# acs.net
KiCad netlist of a schematic drawn in EAGLE
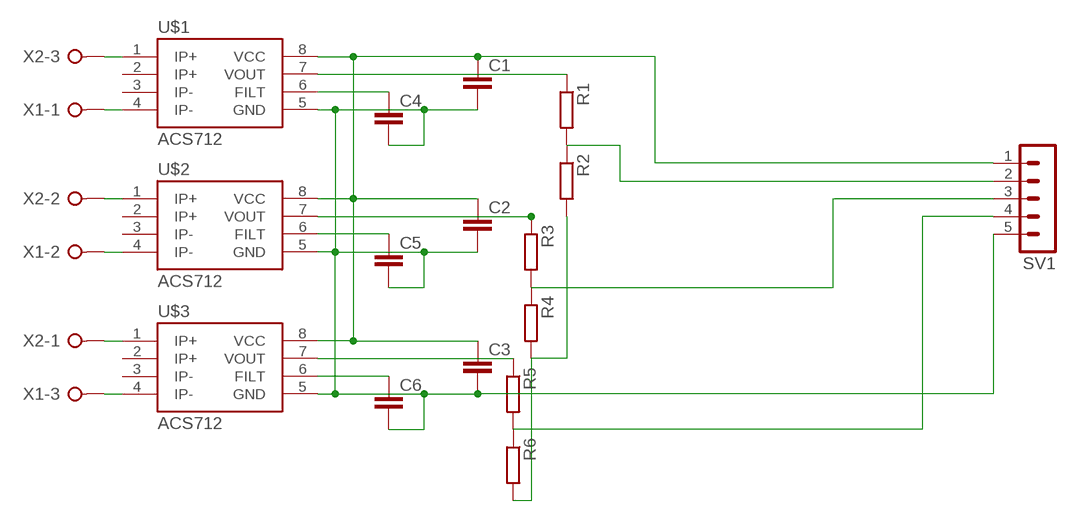
[diagram p0: schematic, sheet 1]

(export (version "E")
  (design (tool "Eeschema 10.0.6"))
  (components
    (comp (ref "C1")
      (value "C-EUC0603")
      (footprint "eagle-import:C0603")
      (libsource (lib "eagle-import") (part "C-EUC0603"))
    )
    (comp (ref "C2")
      (value "C-EUC0603")
      (footprint "eagle-import:C0603")
      (libsource (lib "eagle-import") (part "C-EUC0603"))
    )
    (comp (ref "C3")
      (value "C-EUC0603")
      (footprint "eagle-import:C0603")
      (libsource (lib "eagle-import") (part "C-EUC0603"))
    )
    (comp (ref "C4")
      (value "C-EUC0603")
      (footprint "eagle-import:C0603")
      (libsource (lib "eagle-import") (part "C-EUC0603"))
    )
    (comp (ref "C5")
      (value "C-EUC0603")
      (footprint "eagle-import:C0603")
      (libsource (lib "eagle-import") (part "C-EUC0603"))
    )
    (comp (ref "C6")
      (value "C-EUC0603")
      (footprint "eagle-import:C0603")
      (libsource (lib "eagle-import") (part "C-EUC0603"))
    )
    (comp (ref "R1")
      (value "R-EU_R0603")
      (footprint "eagle-import:R0603")
      (libsource (lib "eagle-import") (part "R-EU_R0603"))
    )
    (comp (ref "R2")
      (value "R-EU_R0603")
      (footprint "eagle-import:R0603")
      (libsource (lib "eagle-import") (part "R-EU_R0603"))
    )
    (comp (ref "R3")
      (value "R-EU_R0603")
      (footprint "eagle-import:R0603")
      (libsource (lib "eagle-import") (part "R-EU_R0603"))
    )
    (comp (ref "R4")
      (value "R-EU_R0603")
      (footprint "eagle-import:R0603")
      (libsource (lib "eagle-import") (part "R-EU_R0603"))
    )
    (comp (ref "R5")
      (value "R-EU_R0603")
      (footprint "eagle-import:R0603")
      (libsource (lib "eagle-import") (part "R-EU_R0603"))
    )
    (comp (ref "R6")
      (value "R-EU_R0603")
      (footprint "eagle-import:R0603")
      (libsource (lib "eagle-import") (part "R-EU_R0603"))
    )
    (comp (ref "SV1")
      (value "MA05-1")
      (footprint "eagle-import:MA05-1")
      (libsource (lib "eagle-import") (part "MA05-1"))
    )
    (comp (ref "U$1")
      (value "ACS712")
      (footprint "eagle-import:SO08")
      (libsource (lib "eagle-import") (part "ACS712"))
    )
    (comp (ref "U$2")
      (value "ACS712")
      (footprint "eagle-import:SO08")
      (libsource (lib "eagle-import") (part "ACS712"))
    )
    (comp (ref "U$3")
      (value "ACS712")
      (footprint "eagle-import:SO08")
      (libsource (lib "eagle-import") (part "ACS712"))
    )
    (comp (ref "X1")
      (value "W237-03P")
      (footprint "eagle-import:W237-133")
      (libsource (lib "eagle-import") (part "W237-03P"))
    )
    (comp (ref "X2")
      (value "W237-03P")
      (footprint "eagle-import:W237-133")
      (libsource (lib "eagle-import") (part "W237-03P"))
    )
  )
  (nets
    (net (code "1") (name "Net-(R1-Pad2)") (class "Default")
      (node (ref "R1") (pin "2") (pinfunction "2_2") (pintype "passive"))
      (node (ref "R2") (pin "1") (pinfunction "1_1") (pintype "passive"))
      (node (ref "SV1") (pin "2") (pinfunction "2_2") (pintype "passive"))
    )
    (net (code "2") (name "Net-(R2-Pad2)") (class "Default")
      (node (ref "R2") (pin "2") (pinfunction "2_2") (pintype "passive"))
      (node (ref "R4") (pin "2") (pinfunction "2_2") (pintype "passive"))
      (node (ref "R6") (pin "2") (pinfunction "2_2") (pintype "passive"))
    )
    (net (code "3") (name "Net-(R3-Pad2)") (class "Default")
      (node (ref "R3") (pin "2") (pinfunction "2_2") (pintype "passive"))
      (node (ref "R4") (pin "1") (pinfunction "1_1") (pintype "passive"))
      (node (ref "SV1") (pin "3") (pinfunction "3_3") (pintype "passive"))
    )
    (net (code "4") (name "Net-(R5-Pad2)") (class "Default")
      (node (ref "R5") (pin "2") (pinfunction "2_2") (pintype "passive"))
      (node (ref "R6") (pin "1") (pinfunction "1_1") (pintype "passive"))
      (node (ref "SV1") (pin "4") (pinfunction "4_4") (pintype "passive"))
    )
    (net (code "5") (name "Net-(U$1-FILT)") (class "Default")
      (node (ref "C4") (pin "1") (pinfunction "1_1") (pintype "passive"))
      (node (ref "U$1") (pin "6") (pinfunction "FILT_6") (pintype "bidirectional"))
    )
    (net (code "6") (name "Net-(U$1-GND)") (class "Default")
      (node (ref "C1") (pin "2") (pinfunction "2_2") (pintype "passive"))
      (node (ref "C2") (pin "2") (pinfunction "2_2") (pintype "passive"))
      (node (ref "C3") (pin "2") (pinfunction "2_2") (pintype "passive"))
      (node (ref "C4") (pin "2") (pinfunction "2_2") (pintype "passive"))
      (node (ref "C5") (pin "2") (pinfunction "2_2") (pintype "passive"))
      (node (ref "C6") (pin "2") (pinfunction "2_2") (pintype "passive"))
      (node (ref "SV1") (pin "5") (pinfunction "5_5") (pintype "passive"))
      (node (ref "U$1") (pin "5") (pinfunction "GND_5") (pintype "bidirectional"))
      (node (ref "U$2") (pin "5") (pinfunction "GND_5") (pintype "bidirectional"))
      (node (ref "U$3") (pin "5") (pinfunction "GND_5") (pintype "bidirectional"))
    )
    (net (code "7") (name "Net-(U$1-VCC)") (class "Default")
      (node (ref "C1") (pin "1") (pinfunction "1_1") (pintype "passive"))
      (node (ref "C2") (pin "1") (pinfunction "1_1") (pintype "passive"))
      (node (ref "C3") (pin "1") (pinfunction "1_1") (pintype "passive"))
      (node (ref "SV1") (pin "1") (pinfunction "1_1") (pintype "passive"))
      (node (ref "U$1") (pin "8") (pinfunction "VCC_8") (pintype "bidirectional"))
      (node (ref "U$2") (pin "8") (pinfunction "VCC_8") (pintype "bidirectional"))
      (node (ref "U$3") (pin "8") (pinfunction "VCC_8") (pintype "bidirectional"))
    )
    (net (code "8") (name "Net-(U$1-VOUT)") (class "Default")
      (node (ref "R1") (pin "1") (pinfunction "1_1") (pintype "passive"))
      (node (ref "U$1") (pin "7") (pinfunction "VOUT_7") (pintype "bidirectional"))
    )
    (net (code "9") (name "Net-(U$2-FILT)") (class "Default")
      (node (ref "C5") (pin "1") (pinfunction "1_1") (pintype "passive"))
      (node (ref "U$2") (pin "6") (pinfunction "FILT_6") (pintype "bidirectional"))
    )
    (net (code "10") (name "Net-(U$2-VOUT)") (class "Default")
      (node (ref "R3") (pin "1") (pinfunction "1_1") (pintype "passive"))
      (node (ref "U$2") (pin "7") (pinfunction "VOUT_7") (pintype "bidirectional"))
    )
    (net (code "11") (name "Net-(U$3-FILT)") (class "Default")
      (node (ref "C6") (pin "1") (pinfunction "1_1") (pintype "passive"))
      (node (ref "U$3") (pin "6") (pinfunction "FILT_6") (pintype "bidirectional"))
    )
    (net (code "12") (name "Net-(U$3-VOUT)") (class "Default")
      (node (ref "R5") (pin "1") (pinfunction "1_1") (pintype "passive"))
      (node (ref "U$3") (pin "7") (pinfunction "VOUT_7") (pintype "bidirectional"))
    )
    (net (code "13") (name "Net-(X1A-KL)") (class "Default")
      (node (ref "U$1") (pin "4") (pinfunction "IP-_4") (pintype "bidirectional"))
      (node (ref "X1") (pin "1") (pinfunction "KL_1") (pintype "passive"))
    )
    (net (code "14") (name "Net-(X1B-KL)") (class "Default")
      (node (ref "U$2") (pin "4") (pinfunction "IP-_4") (pintype "bidirectional"))
      (node (ref "X1") (pin "2") (pinfunction "KL_2") (pintype "passive"))
    )
    (net (code "15") (name "Net-(X1C-KL)") (class "Default")
      (node (ref "U$3") (pin "4") (pinfunction "IP-_4") (pintype "bidirectional"))
      (node (ref "X1") (pin "3") (pinfunction "KL_3") (pintype "passive"))
    )
    (net (code "16") (name "Net-(X2A-KL)") (class "Default")
      (node (ref "U$3") (pin "1") (pinfunction "IP+_1") (pintype "bidirectional"))
      (node (ref "X2") (pin "1") (pinfunction "KL_1") (pintype "passive"))
    )
    (net (code "17") (name "Net-(X2B-KL)") (class "Default")
      (node (ref "U$2") (pin "1") (pinfunction "IP+_1") (pintype "bidirectional"))
      (node (ref "X2") (pin "2") (pinfunction "KL_2") (pintype "passive"))
    )
    (net (code "18") (name "Net-(X2C-KL)") (class "Default")
      (node (ref "U$1") (pin "1") (pinfunction "IP+_1") (pintype "bidirectional"))
      (node (ref "X2") (pin "3") (pinfunction "KL_3") (pintype "passive"))
    )
    (net (code "19") (name "unconnected-(U$1-IP+-Pad2)") (class "Default")
      (node (ref "U$1") (pin "2") (pinfunction "IP+_2") (pintype "bidirectional"))
    )
    (net (code "20") (name "unconnected-(U$1-IP--Pad3)") (class "Default")
      (node (ref "U$1") (pin "3") (pinfunction "IP-_3") (pintype "bidirectional"))
    )
    (net (code "21") (name "unconnected-(U$2-IP+-Pad2)") (class "Default")
      (node (ref "U$2") (pin "2") (pinfunction "IP+_2") (pintype "bidirectional"))
    )
    (net (code "22") (name "unconnected-(U$2-IP--Pad3)") (class "Default")
      (node (ref "U$2") (pin "3") (pinfunction "IP-_3") (pintype "bidirectional"))
    )
    (net (code "23") (name "unconnected-(U$3-IP+-Pad2)") (class "Default")
      (node (ref "U$3") (pin "2") (pinfunction "IP+_2") (pintype "bidirectional"))
    )
    (net (code "24") (name "unconnected-(U$3-IP--Pad3)") (class "Default")
      (node (ref "U$3") (pin "3") (pinfunction "IP-_3") (pintype "bidirectional"))
    )
  )
)
